# Mikrokontroler.net
KiCad netlist of a schematic drawn in Altium Designer
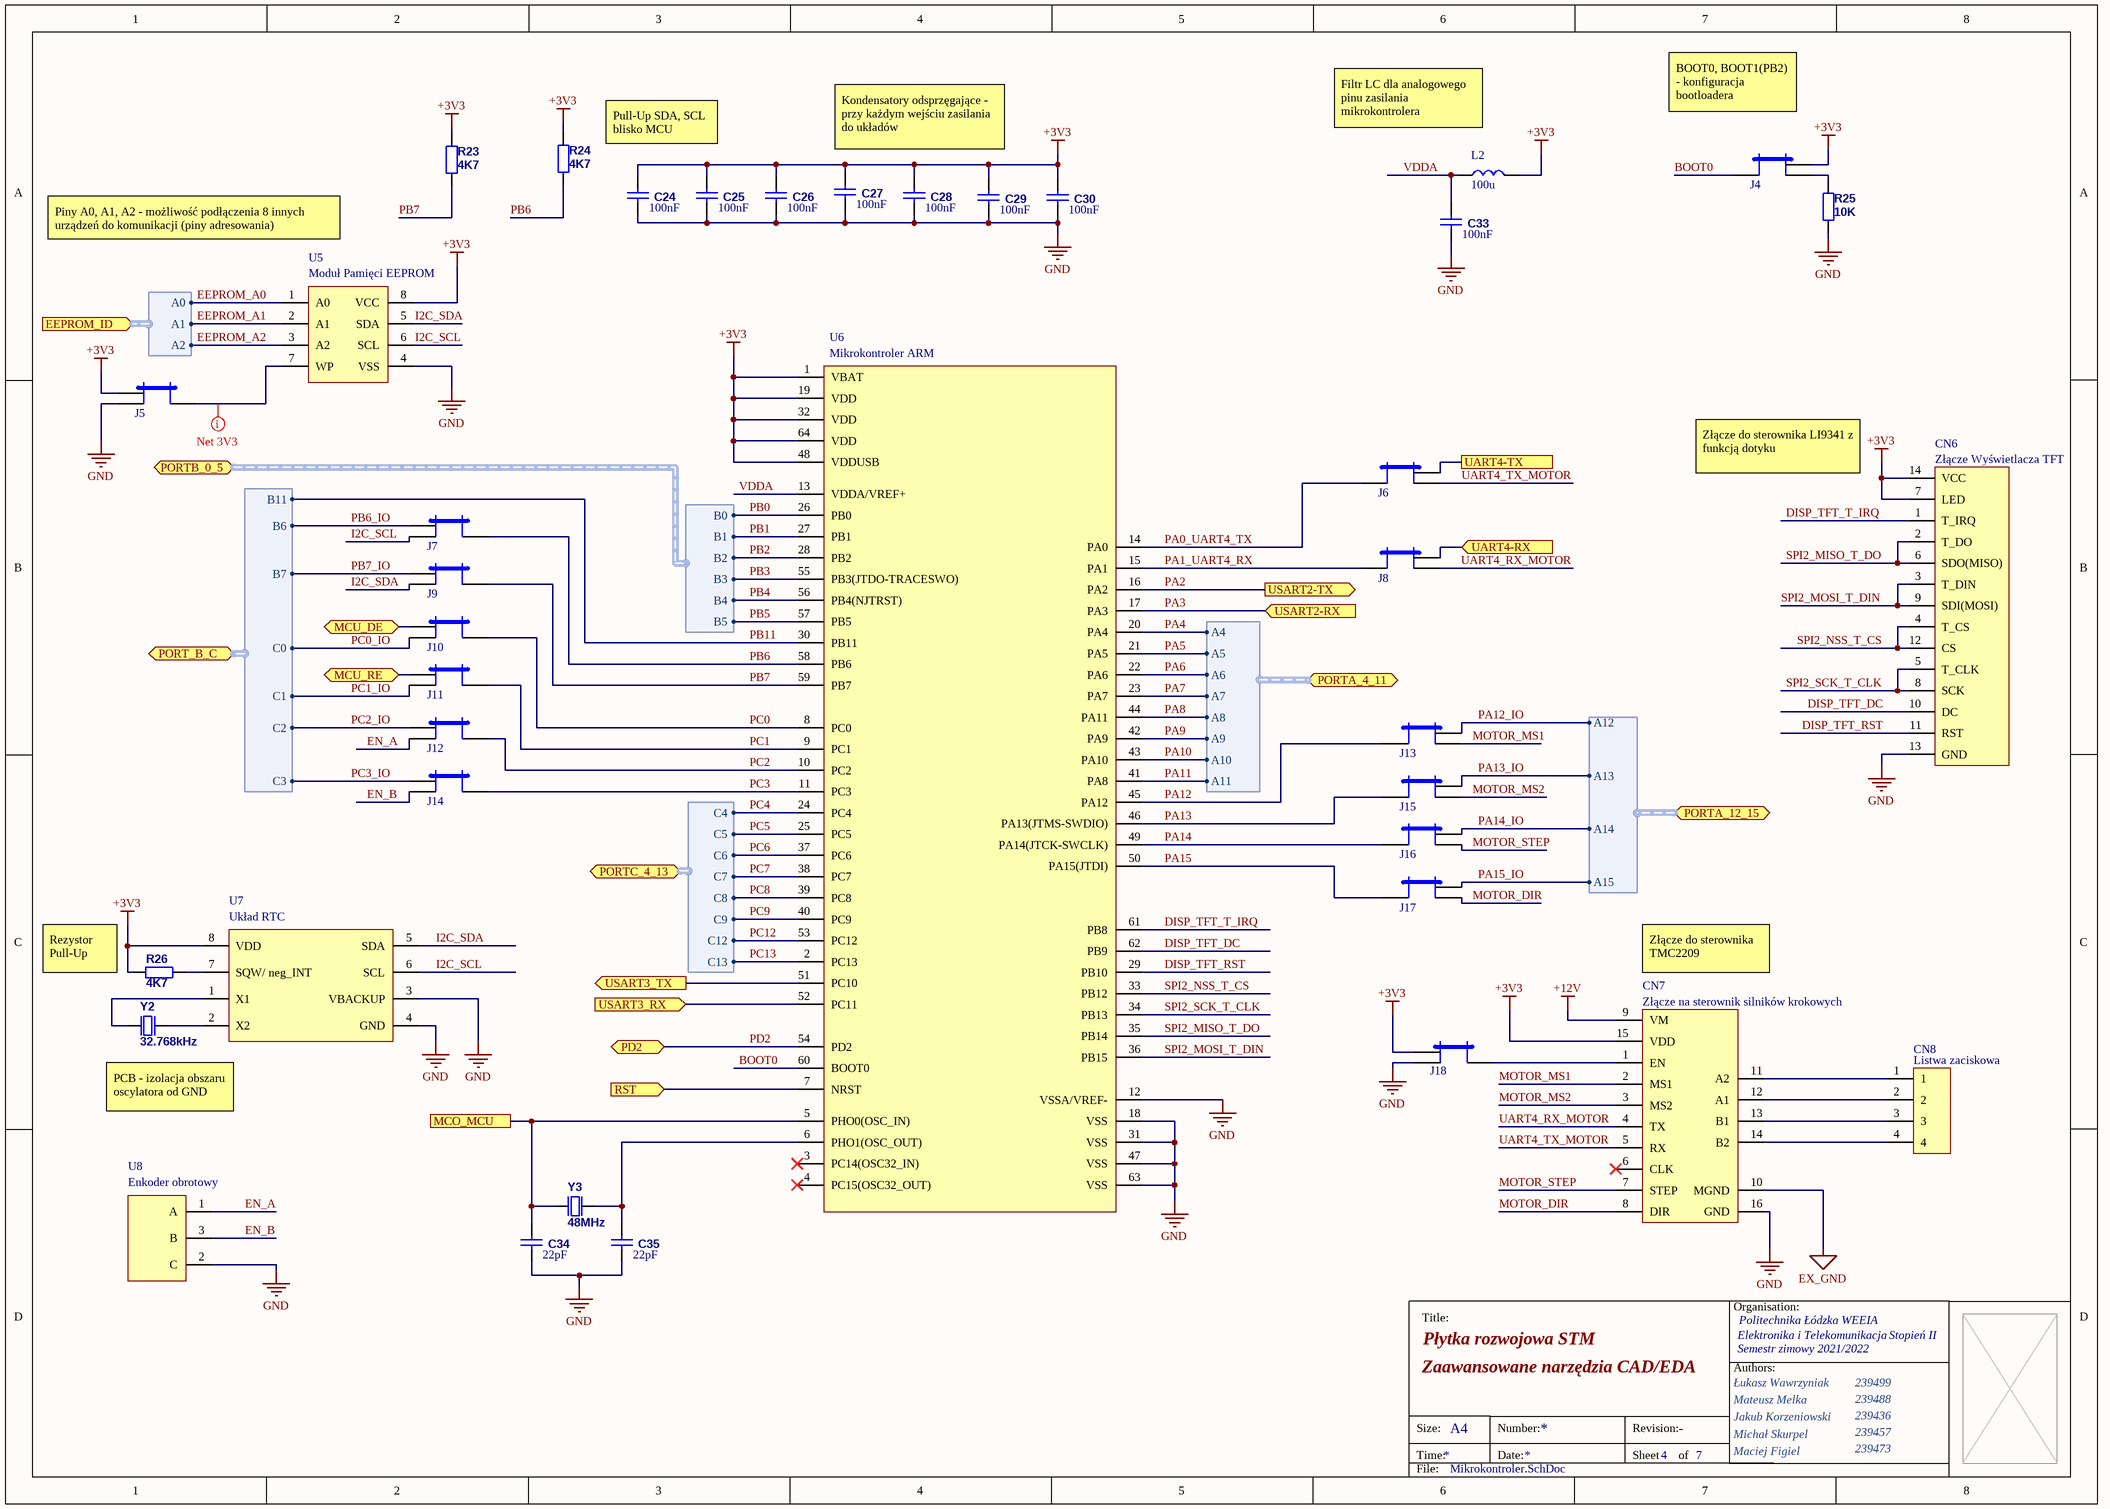
[diagram p0: Mikrokontroler.SchDoc]

(export (version "E")
  (design (tool "Eeschema 10.0.6"))
  (components
    (comp (ref "C24")
      (value "100nF")
      (footprint "PCB1:0805")
      (description "Ceramic capacitor MLCC SMD ±1%")
      (libsource (lib "capacitors") (part "Cap"))
    )
    (comp (ref "C25")
      (value "100nF")
      (footprint "PCB1:0805")
      (description "Ceramic capacitor MLCC SMD ±1%")
      (libsource (lib "capacitors") (part "Cap"))
    )
    (comp (ref "C26")
      (value "100nF")
      (footprint "PCB1:0805")
      (description "Ceramic capacitor MLCC SMD ±1%")
      (libsource (lib "capacitors") (part "Cap"))
    )
    (comp (ref "C27")
      (value "100nF")
      (footprint "PCB1:0805")
      (description "Ceramic capacitor MLCC SMD ±1%")
      (libsource (lib "capacitors") (part "Cap"))
    )
    (comp (ref "C28")
      (value "100nF")
      (footprint "PCB1:0805")
      (description "Ceramic capacitor MLCC SMD ±1%")
      (libsource (lib "capacitors") (part "Cap"))
    )
    (comp (ref "C29")
      (value "100nF")
      (footprint "PCB1:0805")
      (description "Ceramic capacitor MLCC SMD ±1%")
      (libsource (lib "capacitors") (part "Cap"))
    )
    (comp (ref "C30")
      (value "100nF")
      (footprint "PCB1:0805")
      (description "Ceramic capacitor MLCC SMD ±1%")
      (libsource (lib "capacitors") (part "Cap"))
    )
    (comp (ref "C33")
      (value "100nF")
      (footprint "PCB1:0805")
      (description "Ceramic capacitor MLCC SMD ±1%")
      (libsource (lib "capacitors") (part "Cap"))
    )
    (comp (ref "C34")
      (value "22pF")
      (footprint "PCB1:0805")
      (description "Ceramic capacitor MLCC SMD ±1%")
      (libsource (lib "capacitors") (part "Cap"))
    )
    (comp (ref "C35")
      (value "22pF")
      (footprint "PCB1:0805")
      (description "Ceramic capacitor MLCC SMD ±1%")
      (libsource (lib "capacitors") (part "Cap"))
    )
    (comp (ref "CN6")
      (value "Złącze Wyświetlacza TFT")
      (footprint "Display_TFT_Socket_1x14_Raster_2_54mm")
      (libsource (lib "Lib_ZCAD_plytka_rozwojowa") (part "DISPLAY_TFT_Socket_1x14"))
    )
    (comp (ref "CN7")
      (value "Złącze na sterownik silników krokowych")
      (footprint "Step_motor_Socket_TMC2209")
      (libsource (lib "Lib_ZCAD_plytka_rozwojowa") (part "Step_motor_Socket_TMC2209"))
    )
    (comp (ref "CN8")
      (value "Listwa zaciskowa")
      (footprint "TE_282836-4")
      (libsource (lib "Lib_ZCAD_plytka_rozwojowa") (part "Terminal_block_1x4"))
    )
    (comp (ref "J4")
      (value "Zworka")
      (footprint "Jumper_1x3_Raster_2_54mm")
      (libsource (lib "Lib_ZCAD_plytka_rozwojowa") (part "Jumper1x3"))
    )
    (comp (ref "J5")
      (value "Zworka")
      (footprint "Jumper_1x3_Raster_2_54mm")
      (libsource (lib "Lib_ZCAD_plytka_rozwojowa") (part "Jumper1x3"))
    )
    (comp (ref "J6")
      (value "Zworka")
      (footprint "Jumper_1x3_Raster_2_54mm")
      (libsource (lib "Lib_ZCAD_plytka_rozwojowa") (part "Jumper1x3"))
    )
    (comp (ref "J7")
      (value "Zworka")
      (footprint "Jumper_1x3_Raster_2_54mm")
      (libsource (lib "Lib_ZCAD_plytka_rozwojowa") (part "Jumper1x3"))
    )
    (comp (ref "J8")
      (value "Zworka")
      (footprint "Jumper_1x3_Raster_2_54mm")
      (libsource (lib "Lib_ZCAD_plytka_rozwojowa") (part "Jumper1x3"))
    )
    (comp (ref "J9")
      (value "Zworka")
      (footprint "Jumper_1x3_Raster_2_54mm")
      (libsource (lib "Lib_ZCAD_plytka_rozwojowa") (part "Jumper1x3"))
    )
    (comp (ref "J10")
      (value "Zworka")
      (footprint "Jumper_1x3_Raster_2_54mm")
      (libsource (lib "Lib_ZCAD_plytka_rozwojowa") (part "Jumper1x3"))
    )
    (comp (ref "J11")
      (value "Zworka")
      (footprint "Jumper_1x3_Raster_2_54mm")
      (libsource (lib "Lib_ZCAD_plytka_rozwojowa") (part "Jumper1x3"))
    )
    (comp (ref "J12")
      (value "Zworka")
      (footprint "Jumper_1x3_Raster_2_54mm")
      (libsource (lib "Lib_ZCAD_plytka_rozwojowa") (part "Jumper1x3"))
    )
    (comp (ref "J13")
      (value "Zworka")
      (footprint "Jumper_1x3_Raster_2_54mm")
      (libsource (lib "Lib_ZCAD_plytka_rozwojowa") (part "Jumper1x3"))
    )
    (comp (ref "J14")
      (value "Zworka")
      (footprint "Jumper_1x3_Raster_2_54mm")
      (libsource (lib "Lib_ZCAD_plytka_rozwojowa") (part "Jumper1x3"))
    )
    (comp (ref "J15")
      (value "Zworka")
      (footprint "Jumper_1x3_Raster_2_54mm")
      (libsource (lib "Lib_ZCAD_plytka_rozwojowa") (part "Jumper1x3"))
    )
    (comp (ref "J16")
      (value "Zworka")
      (footprint "Jumper_1x3_Raster_2_54mm")
      (libsource (lib "Lib_ZCAD_plytka_rozwojowa") (part "Jumper1x3"))
    )
    (comp (ref "J17")
      (value "Zworka")
      (footprint "Jumper_1x3_Raster_2_54mm")
      (libsource (lib "Lib_ZCAD_plytka_rozwojowa") (part "Jumper1x3"))
    )
    (comp (ref "J18")
      (value "Zworka")
      (footprint "Jumper_1x3_Raster_2_54mm")
      (libsource (lib "Lib_ZCAD_plytka_rozwojowa") (part "Jumper1x3"))
    )
    (comp (ref "L2")
      (value "100u")
      (footprint "Coil_Raster_2mm")
      (fields (field (name "Comment") "Coil"))
      (libsource (lib "Lib_ZCAD_plytka_rozwojowa") (part "Coil"))
    )
    (comp (ref "R23")
      (value "4K7")
      (footprint "PCB1:0805")
      (description "Resistor SMD  ±5%")
      (libsource (lib "resistors") (part "Res"))
    )
    (comp (ref "R24")
      (value "4K7")
      (footprint "PCB1:0805")
      (description "Resistor SMD  ±5%")
      (libsource (lib "resistors") (part "Res"))
    )
    (comp (ref "R25")
      (value "10K")
      (footprint "PCB1:0805")
      (description "Resistor SMD  ±5%")
      (libsource (lib "resistors") (part "Res"))
    )
    (comp (ref "R26")
      (value "4K7")
      (footprint "PCB1:0805")
      (description "Resistor SMD  ±5%")
      (libsource (lib "") (part "Res_1"))
    )
    (comp (ref "U5")
      (value "Moduł Pamięci EEPROM")
      (footprint "SOIC127P794X203-8N")
      (libsource (lib "Lib_ZCAD_plytka_rozwojowa") (part "EEPROM_24LC512_I/SN"))
    )
    (comp (ref "U6")
      (value "Mikrokontroler ARM")
      (footprint "QFP50P1200X1200X160-64N")
      (libsource (lib "Lib_ZCAD_plytka_rozwojowa") (part "ARM_Microcontroller_STM32L476RG"))
    )
    (comp (ref "U7")
      (value "Układ RTC")
      (footprint "SOP65P490X110-8N")
      (libsource (lib "Lib_ZCAD_plytka_rozwojowa") (part "RTC_DS1339AU"))
    )
    (comp (ref "U8")
      (value "Enkoder obrotowy")
      (footprint "Encoder_EC12E1220405")
      (libsource (lib "Lib_ZCAD_plytka_rozwojowa") (part "Encoder_EC12E1220405"))
    )
    (comp (ref "Y2")
      (value "32.768kHz")
      (footprint "HC49/4H")
      (description "Crystal Oscillator (20pF)")
      (libsource (lib "quartz_crystals_and_filters") (part "XTAL_2PIN"))
    )
    (comp (ref "Y3")
      (value "48MHz")
      (footprint "HC49/4H")
      (description "Crystal Oscillator (20pF)")
      (libsource (lib "quartz_crystals_and_filters") (part "XTAL_2PIN"))
    )
  )
  (nets
    (net (code "15") (name "+3V3") (class "Default")
      (node (ref "C24") (pin "2") (pinfunction "2_2") (pintype "passive"))
      (node (ref "C25") (pin "2") (pinfunction "2_2") (pintype "passive"))
      (node (ref "C26") (pin "2") (pinfunction "2_2") (pintype "passive"))
      (node (ref "C27") (pin "2") (pinfunction "2_2") (pintype "passive"))
      (node (ref "C28") (pin "2") (pinfunction "2_2") (pintype "passive"))
      (node (ref "C29") (pin "2") (pinfunction "2_2") (pintype "passive"))
      (node (ref "C30") (pin "2") (pinfunction "2_2") (pintype "passive"))
      (node (ref "CN6") (pin "14") (pinfunction "VCC_14") (pintype "passive"))
      (node (ref "CN6") (pin "7") (pinfunction "LED_7") (pintype "passive"))
      (node (ref "CN7") (pin "15") (pinfunction "VDD_15") (pintype "passive"))
      (node (ref "J18") (pin "1") (pinfunction "1_1") (pintype "passive"))
      (node (ref "J4") (pin "1") (pinfunction "1_1") (pintype "passive"))
      (node (ref "J5") (pin "1") (pinfunction "1_1") (pintype "passive"))
      (node (ref "L2") (pin "1") (pintype "passive"))
      (node (ref "R23") (pin "1") (pinfunction "1_1") (pintype "passive"))
      (node (ref "R24") (pin "1") (pinfunction "1_1") (pintype "passive"))
      (node (ref "R26") (pin "2") (pinfunction "2_2") (pintype "passive"))
      (node (ref "U5") (pin "8") (pinfunction "VCC_8") (pintype "passive"))
      (node (ref "U6") (pin "1") (pinfunction "VBAT_1") (pintype "passive"))
      (node (ref "U6") (pin "19") (pinfunction "VDD_19") (pintype "passive"))
      (node (ref "U6") (pin "32") (pinfunction "VDD_32") (pintype "passive"))
      (node (ref "U6") (pin "48") (pinfunction "VDDUSB_48") (pintype "passive"))
      (node (ref "U6") (pin "64") (pinfunction "VDD_64") (pintype "passive"))
      (node (ref "U7") (pin "8") (pinfunction "VDD_8") (pintype "passive"))
    )
    (net (code "16") (name "+12V") (class "Default")
      (node (ref "CN7") (pin "9") (pinfunction "VM_9") (pintype "passive"))
    )
    (net (code "17") (name "/BOOT0") (class "Default")
      (node (ref "J4") (pin "2") (pinfunction "2_2") (pintype "passive"))
      (node (ref "U6") (pin "60") (pinfunction "BOOT0_60") (pintype "passive"))
    )
    (net (code "18") (name "/DISP_TFT_DC") (class "Default")
      (node (ref "CN6") (pin "10") (pinfunction "DC_10") (pintype "passive"))
      (node (ref "U6") (pin "62") (pinfunction "PB9_62") (pintype "passive"))
    )
    (net (code "19") (name "/DISP_TFT_RST") (class "Default")
      (node (ref "CN6") (pin "11") (pinfunction "RST_11") (pintype "passive"))
      (node (ref "U6") (pin "29") (pinfunction "PB10_29") (pintype "passive"))
    )
    (net (code "20") (name "/DISP_TFT_T_IRQ") (class "Default")
      (node (ref "CN6") (pin "1") (pinfunction "T_IRQ_1") (pintype "passive"))
      (node (ref "U6") (pin "61") (pinfunction "PB8_61") (pintype "passive"))
    )
    (net (code "21") (name "/EEPROM_A0") (class "Default")
      (node (ref "U5") (pin "1") (pinfunction "A0_1") (pintype "passive"))
    )
    (net (code "22") (name "/EEPROM_A1") (class "Default")
      (node (ref "U5") (pin "2") (pinfunction "A1_2") (pintype "passive"))
    )
    (net (code "23") (name "/EEPROM_A2") (class "Default")
      (node (ref "U5") (pin "3") (pinfunction "A2_3") (pintype "passive"))
    )
    (net (code "24") (name "/EN_A") (class "Default")
      (node (ref "J12") (pin "3") (pinfunction "1_3") (pintype "passive"))
      (node (ref "U8") (pin "1") (pinfunction "A_1") (pintype "passive"))
    )
    (net (code "25") (name "/EN_B") (class "Default")
      (node (ref "J14") (pin "3") (pinfunction "1_3") (pintype "passive"))
      (node (ref "U8") (pin "3") (pinfunction "B_3") (pintype "passive"))
    )
    (net (code "26") (name "/I2C_SCL") (class "Default")
      (node (ref "J7") (pin "3") (pinfunction "1_3") (pintype "passive"))
      (node (ref "U5") (pin "6") (pinfunction "SCL_6") (pintype "passive"))
      (node (ref "U7") (pin "6") (pinfunction "SCL_6") (pintype "passive"))
    )
    (net (code "27") (name "/I2C_SDA") (class "Default")
      (node (ref "J9") (pin "3") (pinfunction "1_3") (pintype "passive"))
      (node (ref "U5") (pin "5") (pinfunction "SDA_5") (pintype "passive"))
      (node (ref "U7") (pin "5") (pinfunction "SDA_5") (pintype "passive"))
    )
    (net (code "28") (name "/MCO_MCU") (class "Default")
      (node (ref "C34") (pin "2") (pinfunction "2_2") (pintype "passive"))
      (node (ref "U6") (pin "5") (pinfunction "PHO0(OSC_IN)_5") (pintype "passive"))
      (node (ref "Y3") (pin "2") (pinfunction "OSC2_2") (pintype "passive"))
    )
    (net (code "29") (name "/MCU_DE") (class "Default")
      (node (ref "J10") (pin "1") (pinfunction "1_1") (pintype "passive"))
    )
    (net (code "30") (name "/MCU_RE") (class "Default")
      (node (ref "J11") (pin "1") (pinfunction "1_1") (pintype "passive"))
    )
    (net (code "31") (name "/MOTOR_DIR") (class "Default")
      (node (ref "CN7") (pin "8") (pinfunction "DIR_8") (pintype "passive"))
      (node (ref "J17") (pin "3") (pinfunction "1_3") (pintype "passive"))
    )
    (net (code "32") (name "/MOTOR_MS1") (class "Default")
      (node (ref "CN7") (pin "2") (pinfunction "MS1_2") (pintype "passive"))
      (node (ref "J13") (pin "3") (pinfunction "1_3") (pintype "passive"))
    )
    (net (code "33") (name "/MOTOR_MS2") (class "Default")
      (node (ref "CN7") (pin "3") (pinfunction "MS2_3") (pintype "passive"))
      (node (ref "J15") (pin "3") (pinfunction "1_3") (pintype "passive"))
    )
    (net (code "34") (name "/MOTOR_STEP") (class "Default")
      (node (ref "CN7") (pin "7") (pinfunction "STEP_7") (pintype "passive"))
      (node (ref "J16") (pin "3") (pinfunction "1_3") (pintype "passive"))
    )
    (net (code "35") (name "/PA0_UART4_TX") (class "Default")
      (node (ref "J6") (pin "2") (pinfunction "2_2") (pintype "passive"))
      (node (ref "U6") (pin "14") (pinfunction "PA0_14") (pintype "passive"))
    )
    (net (code "36") (name "/PA1_UART4_RX") (class "Default")
      (node (ref "J8") (pin "2") (pinfunction "2_2") (pintype "passive"))
      (node (ref "U6") (pin "15") (pinfunction "PA1_15") (pintype "passive"))
    )
    (net (code "37") (name "/PA2") (class "Default")
      (node (ref "U6") (pin "16") (pinfunction "PA2_16") (pintype "passive"))
    )
    (net (code "38") (name "/PA3") (class "Default")
      (node (ref "U6") (pin "17") (pinfunction "PA3_17") (pintype "passive"))
    )
    (net (code "39") (name "/PA4") (class "Default")
      (node (ref "U6") (pin "20") (pinfunction "PA4_20") (pintype "passive"))
    )
    (net (code "40") (name "/PA5") (class "Default")
      (node (ref "U6") (pin "21") (pinfunction "PA5_21") (pintype "passive"))
    )
    (net (code "41") (name "/PA6") (class "Default")
      (node (ref "U6") (pin "22") (pinfunction "PA6_22") (pintype "passive"))
    )
    (net (code "42") (name "/PA7") (class "Default")
      (node (ref "U6") (pin "23") (pinfunction "PA7_23") (pintype "passive"))
    )
    (net (code "43") (name "/PA8") (class "Default")
      (node (ref "U6") (pin "44") (pinfunction "PA11_44") (pintype "passive"))
    )
    (net (code "44") (name "/PA9") (class "Default")
      (node (ref "U6") (pin "42") (pinfunction "PA9_42") (pintype "passive"))
    )
    (net (code "45") (name "/PA10") (class "Default")
      (node (ref "U6") (pin "43") (pinfunction "PA10_43") (pintype "passive"))
    )
    (net (code "46") (name "/PA11") (class "Default")
      (node (ref "U6") (pin "41") (pinfunction "PA8_41") (pintype "passive"))
    )
    (net (code "47") (name "/PA12") (class "Default")
      (node (ref "J13") (pin "2") (pinfunction "2_2") (pintype "passive"))
      (node (ref "U6") (pin "45") (pinfunction "PA12_45") (pintype "passive"))
    )
    (net (code "48") (name "/PA12_IO") (class "Default")
      (node (ref "J13") (pin "1") (pinfunction "1_1") (pintype "passive"))
    )
    (net (code "49") (name "/PA13") (class "Default")
      (node (ref "J15") (pin "2") (pinfunction "2_2") (pintype "passive"))
      (node (ref "U6") (pin "46") (pinfunction "PA13(JTMS-SWDIO)_46") (pintype "passive"))
    )
    (net (code "50") (name "/PA13_IO") (class "Default")
      (node (ref "J15") (pin "1") (pinfunction "1_1") (pintype "passive"))
    )
    (net (code "51") (name "/PA14") (class "Default")
      (node (ref "J16") (pin "2") (pinfunction "2_2") (pintype "passive"))
      (node (ref "U6") (pin "49") (pinfunction "PA14(JTCK-SWCLK)_49") (pintype "passive"))
    )
    (net (code "52") (name "/PA14_IO") (class "Default")
      (node (ref "J16") (pin "1") (pinfunction "1_1") (pintype "passive"))
    )
    (net (code "53") (name "/PA15") (class "Default")
      (node (ref "J17") (pin "2") (pinfunction "2_2") (pintype "passive"))
      (node (ref "U6") (pin "50") (pinfunction "PA15(JTDI)_50") (pintype "passive"))
    )
    (net (code "54") (name "/PA15_IO") (class "Default")
      (node (ref "J17") (pin "1") (pinfunction "1_1") (pintype "passive"))
    )
    (net (code "55") (name "/PB0") (class "Default")
      (node (ref "U6") (pin "26") (pinfunction "PB0_26") (pintype "passive"))
    )
    (net (code "56") (name "/PB1") (class "Default")
      (node (ref "U6") (pin "27") (pinfunction "PB1_27") (pintype "passive"))
    )
    (net (code "57") (name "/PB2") (class "Default")
      (node (ref "U6") (pin "28") (pinfunction "PB2_28") (pintype "passive"))
    )
    (net (code "58") (name "/PB3") (class "Default")
      (node (ref "U6") (pin "55") (pinfunction "PB3(JTDO-TRACESWO)_55") (pintype "passive"))
    )
    (net (code "59") (name "/PB4") (class "Default")
      (node (ref "U6") (pin "56") (pinfunction "PB4(NJTRST)_56") (pintype "passive"))
    )
    (net (code "60") (name "/PB5") (class "Default")
      (node (ref "U6") (pin "57") (pinfunction "PB5_57") (pintype "passive"))
    )
    (net (code "61") (name "/PB6") (class "Default")
      (node (ref "J7") (pin "2") (pinfunction "2_2") (pintype "passive"))
      (node (ref "R24") (pin "2") (pinfunction "2_2") (pintype "passive"))
      (node (ref "U6") (pin "58") (pinfunction "PB6_58") (pintype "passive"))
    )
    (net (code "62") (name "/PB6_IO") (class "Default")
      (node (ref "J7") (pin "1") (pinfunction "1_1") (pintype "passive"))
    )
    (net (code "63") (name "/PB7") (class "Default")
      (node (ref "J9") (pin "2") (pinfunction "2_2") (pintype "passive"))
      (node (ref "R23") (pin "2") (pinfunction "2_2") (pintype "passive"))
      (node (ref "U6") (pin "59") (pinfunction "PB7_59") (pintype "passive"))
    )
    (net (code "64") (name "/PB7_IO") (class "Default")
      (node (ref "J9") (pin "1") (pinfunction "1_1") (pintype "passive"))
    )
    (net (code "65") (name "/PB11") (class "Default")
      (node (ref "U6") (pin "30") (pinfunction "PB11_30") (pintype "passive"))
    )
    (net (code "66") (name "/PC0") (class "Default")
      (node (ref "J10") (pin "2") (pinfunction "2_2") (pintype "passive"))
      (node (ref "U6") (pin "8") (pinfunction "PC0_8") (pintype "passive"))
    )
    (net (code "67") (name "/PC0_IO") (class "Default")
      (node (ref "J10") (pin "3") (pinfunction "1_3") (pintype "passive"))
    )
    (net (code "68") (name "/PC1") (class "Default")
      (node (ref "J11") (pin "2") (pinfunction "2_2") (pintype "passive"))
      (node (ref "U6") (pin "9") (pinfunction "PC1_9") (pintype "passive"))
    )
    (net (code "69") (name "/PC1_IO") (class "Default")
      (node (ref "J11") (pin "3") (pinfunction "1_3") (pintype "passive"))
    )
    (net (code "70") (name "/PC2") (class "Default")
      (node (ref "J12") (pin "2") (pinfunction "2_2") (pintype "passive"))
      (node (ref "U6") (pin "10") (pinfunction "PC2_10") (pintype "passive"))
    )
    (net (code "71") (name "/PC2_IO") (class "Default")
      (node (ref "J12") (pin "1") (pinfunction "1_1") (pintype "passive"))
    )
    (net (code "72") (name "/PC3") (class "Default")
      (node (ref "J14") (pin "2") (pinfunction "2_2") (pintype "passive"))
      (node (ref "U6") (pin "11") (pinfunction "PC3_11") (pintype "passive"))
    )
    (net (code "73") (name "/PC3_IO") (class "Default")
      (node (ref "J14") (pin "1") (pinfunction "1_1") (pintype "passive"))
    )
    (net (code "74") (name "/PC4") (class "Default")
      (node (ref "U6") (pin "24") (pinfunction "PC4_24") (pintype "passive"))
    )
    (net (code "75") (name "/PC5") (class "Default")
      (node (ref "U6") (pin "25") (pinfunction "PC5_25") (pintype "passive"))
    )
    (net (code "76") (name "/PC6") (class "Default")
      (node (ref "U6") (pin "37") (pinfunction "PC6_37") (pintype "passive"))
    )
    (net (code "77") (name "/PC7") (class "Default")
      (node (ref "U6") (pin "38") (pinfunction "PC7_38") (pintype "passive"))
    )
    (net (code "78") (name "/PC8") (class "Default")
      (node (ref "U6") (pin "39") (pinfunction "PC8_39") (pintype "passive"))
    )
    (net (code "79") (name "/PC9") (class "Default")
      (node (ref "U6") (pin "40") (pinfunction "PC9_40") (pintype "passive"))
    )
    (net (code "80") (name "/PC12") (class "Default")
      (node (ref "U6") (pin "53") (pinfunction "PC12_53") (pintype "passive"))
    )
    (net (code "81") (name "/PC13") (class "Default")
      (node (ref "U6") (pin "2") (pinfunction "PC13_2") (pintype "passive"))
    )
    (net (code "82") (name "/PD2") (class "Default")
      (node (ref "U6") (pin "54") (pinfunction "PD2_54") (pintype "passive"))
    )
    (net (code "83") (name "/RST") (class "Default")
      (node (ref "U6") (pin "7") (pinfunction "NRST_7") (pintype "passive"))
    )
    (net (code "84") (name "/SPI2_MISO_T_DO") (class "Default")
      (node (ref "CN6") (pin "2") (pinfunction "T_DO_2") (pintype "passive"))
      (node (ref "CN6") (pin "6") (pinfunction "SDO(MISO)_6") (pintype "passive"))
      (node (ref "U6") (pin "35") (pinfunction "PB14_35") (pintype "passive"))
    )
    (net (code "85") (name "/SPI2_MOSI_T_DIN") (class "Default")
      (node (ref "CN6") (pin "3") (pinfunction "T_DIN_3") (pintype "passive"))
      (node (ref "CN6") (pin "9") (pinfunction "SDI(MOSI)_9") (pintype "passive"))
      (node (ref "U6") (pin "36") (pinfunction "PB15_36") (pintype "passive"))
    )
    (net (code "86") (name "/SPI2_NSS_T_CS") (class "Default")
      (node (ref "CN6") (pin "12") (pinfunction "CS_12") (pintype "passive"))
      (node (ref "CN6") (pin "4") (pinfunction "T_CS_4") (pintype "passive"))
      (node (ref "U6") (pin "33") (pinfunction "PB12_33") (pintype "passive"))
    )
    (net (code "87") (name "/SPI2_SCK_T_CLK") (class "Default")
      (node (ref "CN6") (pin "5") (pinfunction "T_CLK_5") (pintype "passive"))
      (node (ref "CN6") (pin "8") (pinfunction "SCK_8") (pintype "passive"))
      (node (ref "U6") (pin "34") (pinfunction "PB13_34") (pintype "passive"))
    )
    (net (code "88") (name "/UART4-RX") (class "Default")
      (node (ref "J8") (pin "1") (pinfunction "1_1") (pintype "passive"))
    )
    (net (code "89") (name "/UART4-TX") (class "Default")
      (node (ref "J6") (pin "1") (pinfunction "1_1") (pintype "passive"))
    )
    (net (code "90") (name "/UART4_RX_MOTOR") (class "Default")
      (node (ref "CN7") (pin "4") (pinfunction "TX_4") (pintype "passive"))
      (node (ref "J8") (pin "3") (pinfunction "1_3") (pintype "passive"))
    )
    (net (code "91") (name "/UART4_TX_MOTOR") (class "Default")
      (node (ref "CN7") (pin "5") (pinfunction "RX_5") (pintype "passive"))
      (node (ref "J6") (pin "3") (pinfunction "1_3") (pintype "passive"))
    )
    (net (code "92") (name "/USART3_RX") (class "Default")
      (node (ref "U6") (pin "52") (pinfunction "PC11_52") (pintype "passive"))
    )
    (net (code "93") (name "/USART3_TX") (class "Default")
      (node (ref "U6") (pin "51") (pinfunction "PC10_51") (pintype "passive"))
    )
    (net (code "94") (name "/VDDA") (class "Default")
      (node (ref "C33") (pin "2") (pinfunction "2_2") (pintype "passive"))
      (node (ref "L2") (pin "2") (pintype "passive"))
      (node (ref "U6") (pin "13") (pinfunction "VDDA/VREF+_13") (pintype "passive"))
    )
    (net (code "101") (name "EX_GND") (class "Default")
      (node (ref "CN7") (pin "10") (pinfunction "MGND_10") (pintype "passive"))
    )
    (net (code "102") (name "GND") (class "Default")
      (node (ref "C24") (pin "1") (pinfunction "1_1") (pintype "passive"))
      (node (ref "C25") (pin "1") (pinfunction "1_1") (pintype "passive"))
      (node (ref "C26") (pin "1") (pinfunction "1_1") (pintype "passive"))
      (node (ref "C27") (pin "1") (pinfunction "1_1") (pintype "passive"))
      (node (ref "C28") (pin "1") (pinfunction "1_1") (pintype "passive"))
      (node (ref "C29") (pin "1") (pinfunction "1_1") (pintype "passive"))
      (node (ref "C30") (pin "1") (pinfunction "1_1") (pintype "passive"))
      (node (ref "C33") (pin "1") (pinfunction "1_1") (pintype "passive"))
      (node (ref "C34") (pin "1") (pinfunction "1_1") (pintype "passive"))
      (node (ref "C35") (pin "1") (pinfunction "1_1") (pintype "passive"))
      (node (ref "CN6") (pin "13") (pinfunction "GND_13") (pintype "passive"))
      (node (ref "CN7") (pin "16") (pinfunction "GND_16") (pintype "passive"))
      (node (ref "J18") (pin "3") (pinfunction "1_3") (pintype "passive"))
      (node (ref "J5") (pin "3") (pinfunction "1_3") (pintype "passive"))
      (node (ref "R25") (pin "2") (pinfunction "2_2") (pintype "passive"))
      (node (ref "U5") (pin "4") (pinfunction "VSS_4") (pintype "passive"))
      (node (ref "U6") (pin "12") (pinfunction "VSSA/VREF-_12") (pintype "passive"))
      (node (ref "U6") (pin "18") (pinfunction "VSS_18") (pintype "passive"))
      (node (ref "U6") (pin "31") (pinfunction "VSS_31") (pintype "passive"))
      (node (ref "U6") (pin "47") (pinfunction "VSS_47") (pintype "passive"))
      (node (ref "U6") (pin "63") (pinfunction "VSS_63") (pintype "passive"))
      (node (ref "U7") (pin "3") (pinfunction "VBACKUP_3") (pintype "passive"))
      (node (ref "U7") (pin "4") (pinfunction "GND_4") (pintype "passive"))
      (node (ref "U8") (pin "2") (pinfunction "C_2") (pintype "passive"))
    )
    (net (code "103") (name "Net-(CN7-A1)") (class "Default")
      (node (ref "CN7") (pin "12") (pinfunction "A1_12") (pintype "passive"))
      (node (ref "CN8") (pin "2") (pinfunction "2_2") (pintype "passive"))
    )
    (net (code "104") (name "Net-(CN7-A2)") (class "Default")
      (node (ref "CN7") (pin "11") (pinfunction "A2_11") (pintype "passive"))
      (node (ref "CN8") (pin "1") (pinfunction "1_1") (pintype "passive"))
    )
    (net (code "105") (name "Net-(CN7-B1)") (class "Default")
      (node (ref "CN7") (pin "13") (pinfunction "B1_13") (pintype "passive"))
      (node (ref "CN8") (pin "3") (pinfunction "3_3") (pintype "passive"))
    )
    (net (code "106") (name "Net-(CN7-B2)") (class "Default")
      (node (ref "CN7") (pin "14") (pinfunction "B2_14") (pintype "passive"))
      (node (ref "CN8") (pin "4") (pinfunction "4_4") (pintype "passive"))
    )
    (net (code "107") (name "Net-(CN7-EN)") (class "Default")
      (node (ref "CN7") (pin "1") (pinfunction "EN_1") (pintype "passive"))
      (node (ref "J18") (pin "2") (pinfunction "2_2") (pintype "passive"))
    )
    (net (code "108") (name "Net-(J4-1-Pad3)") (class "Default")
      (node (ref "J4") (pin "3") (pinfunction "1_3") (pintype "passive"))
      (node (ref "R25") (pin "1") (pinfunction "1_1") (pintype "passive"))
    )
    (net (code "109") (name "Net-(U5-WP)") (class "Default")
      (node (ref "J5") (pin "2") (pinfunction "2_2") (pintype "passive"))
      (node (ref "U5") (pin "7") (pinfunction "WP_7") (pintype "passive"))
    )
    (net (code "110") (name "Net-(U6-PHO1(OSC_OUT))") (class "Default")
      (node (ref "C35") (pin "2") (pinfunction "2_2") (pintype "passive"))
      (node (ref "U6") (pin "6") (pinfunction "PHO1(OSC_OUT)_6") (pintype "passive"))
      (node (ref "Y3") (pin "1") (pinfunction "OSC1_1") (pintype "passive"))
    )
    (net (code "111") (name "Net-(U7-SQW{slash}_neg_INT)") (class "Default")
      (node (ref "R26") (pin "1") (pinfunction "1_1") (pintype "passive"))
      (node (ref "U7") (pin "7") (pinfunction "SQW/_neg_INT_7") (pintype "passive"))
    )
    (net (code "112") (name "Net-(U7-X1)") (class "Default")
      (node (ref "U7") (pin "1") (pinfunction "X1_1") (pintype "passive"))
      (node (ref "Y2") (pin "2") (pinfunction "OSC2_2") (pintype "passive"))
    )
    (net (code "113") (name "Net-(U7-X2)") (class "Default")
      (node (ref "U7") (pin "2") (pinfunction "X2_2") (pintype "passive"))
      (node (ref "Y2") (pin "1") (pinfunction "OSC1_1") (pintype "passive"))
    )
    (net (code "114") (name "unconnected-(CN7-CLK-Pad6)") (class "Default")
      (node (ref "CN7") (pin "6") (pinfunction "CLK_6") (pintype "passive+no_connect"))
    )
    (net (code "115") (name "unconnected-(U6-PC14(OSC32_IN)-Pad3)") (class "Default")
      (node (ref "U6") (pin "3") (pinfunction "PC14(OSC32_IN)_3") (pintype "passive+no_connect"))
    )
    (net (code "116") (name "unconnected-(U6-PC15(OSC32_OUT)-Pad4)") (class "Default")
      (node (ref "U6") (pin "4") (pinfunction "PC15(OSC32_OUT)_4") (pintype "passive+no_connect"))
    )
  )
)
